# QCopterMV_MCU_Sch.net
KiCad netlist of a schematic drawn in Altium Designer
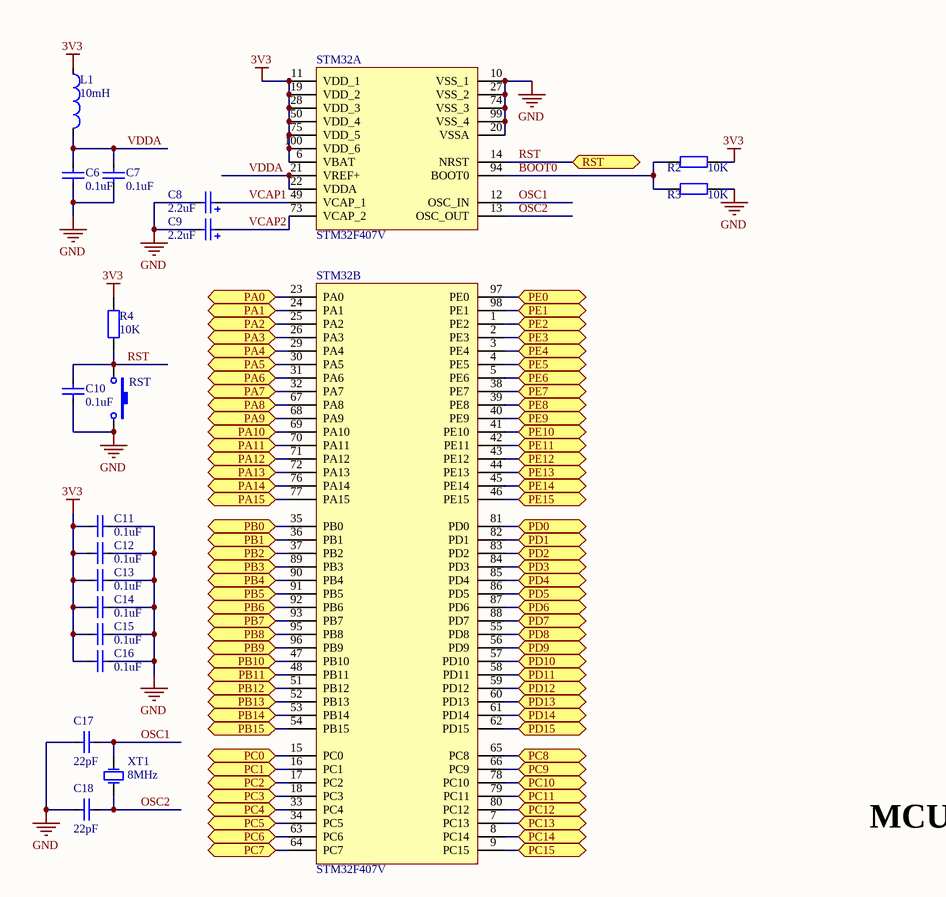
[diagram p0: QCopterMV_MCU_Sch.SchDoc]

(export (version "E")
  (design (tool "Eeschema 10.0.6"))
  (components
    (comp (ref "C6")
      (value "0.1uF")
      (footprint "PCB_Passive:CAP_0603")
      (description "Capacitor")
      (fields (field (name "Comment") "Cap_0603"))
      (libsource (lib "SCH_Passive") (part "Cap_0603"))
    )
    (comp (ref "C7")
      (value "0.1uF")
      (footprint "PCB_Passive:CAP_0603")
      (description "Capacitor")
      (fields (field (name "Comment") "Cap_0603"))
      (libsource (lib "SCH_Passive") (part "Cap_0603"))
    )
    (comp (ref "C8")
      (value "2.2uF")
      (footprint "PCB_Passive:CAP_TAN_P0805")
      (description "Capacitor")
      (fields (field (name "Comment") "Cap_Tan_0805"))
      (libsource (lib "SCH_Passive") (part "Cap_Tan_0805"))
    )
    (comp (ref "C9")
      (value "2.2uF")
      (footprint "PCB_Passive:CAP_TAN_P0805")
      (description "Capacitor")
      (fields (field (name "Comment") "Cap_Tan_0805"))
      (libsource (lib "SCH_Passive") (part "Cap_Tan_0805"))
    )
    (comp (ref "C10")
      (value "0.1uF")
      (footprint "PCB_Passive:CAP_0603")
      (description "Capacitor")
      (fields (field (name "Comment") "Cap_0603"))
      (libsource (lib "SCH_Passive") (part "Cap_0603"))
    )
    (comp (ref "C11")
      (value "0.1uF")
      (footprint "PCB_Passive:CAP_0603")
      (description "Capacitor")
      (fields (field (name "Comment") "Cap_0603"))
      (libsource (lib "SCH_Passive") (part "Cap_0603"))
    )
    (comp (ref "C12")
      (value "0.1uF")
      (footprint "PCB_Passive:CAP_0603")
      (description "Capacitor")
      (fields (field (name "Comment") "Cap_0603"))
      (libsource (lib "SCH_Passive") (part "Cap_0603"))
    )
    (comp (ref "C13")
      (value "0.1uF")
      (footprint "PCB_Passive:CAP_0603")
      (description "Capacitor")
      (fields (field (name "Comment") "Cap_0603"))
      (libsource (lib "SCH_Passive") (part "Cap_0603"))
    )
    (comp (ref "C14")
      (value "0.1uF")
      (footprint "PCB_Passive:CAP_0603")
      (description "Capacitor")
      (fields (field (name "Comment") "Cap_0603"))
      (libsource (lib "SCH_Passive") (part "Cap_0603"))
    )
    (comp (ref "C15")
      (value "0.1uF")
      (footprint "PCB_Passive:CAP_0603")
      (description "Capacitor")
      (fields (field (name "Comment") "Cap_0603"))
      (libsource (lib "SCH_Passive") (part "Cap_0603"))
    )
    (comp (ref "C16")
      (value "0.1uF")
      (footprint "PCB_Passive:CAP_0603")
      (description "Capacitor")
      (fields (field (name "Comment") "Cap_0603"))
      (libsource (lib "SCH_Passive") (part "Cap_0603"))
    )
    (comp (ref "C17")
      (value "22pF")
      (footprint "PCB_Passive:CAP_0603")
      (description "Capacitor")
      (fields (field (name "Comment") "Cap_0603"))
      (libsource (lib "SCH_Passive") (part "Cap_0603"))
    )
    (comp (ref "C18")
      (value "22pF")
      (footprint "PCB_Passive:CAP_0603")
      (description "Capacitor")
      (fields (field (name "Comment") "Cap_0603"))
      (libsource (lib "SCH_Passive") (part "Cap_0603"))
    )
    (comp (ref "L1")
      (value "10mH")
      (footprint "PCB_Passive:IND_0603")
      (description "Inductor")
      (fields (field (name "Comment") "Ind_0603"))
      (libsource (lib "SCH_Passive") (part "Ind_0603"))
    )
    (comp (ref "R2")
      (value "10K")
      (footprint "PCB_Passive:RES_0603")
      (description "Resistor")
      (fields (field (name "Comment") "Res_0603"))
      (libsource (lib "SCH_Passive") (part "Res_0603"))
    )
    (comp (ref "R3")
      (value "10K")
      (footprint "PCB_Passive:RES_0603")
      (description "Resistor")
      (fields (field (name "Comment") "Res_0603"))
      (libsource (lib "SCH_Passive") (part "Res_0603"))
    )
    (comp (ref "R4")
      (value "10K")
      (footprint "PCB_Passive:RES_0603")
      (description "Resistor")
      (fields (field (name "Comment") "Res_0603"))
      (libsource (lib "") (part "Res_0603_1"))
    )
    (comp (ref "RST")
      (value "SW-PB_1")
      (footprint "PCB_Switch:BT_90_T")
      (description "Switch")
      (fields (field (name "PUBLISHER") "Altium Limited"))
      (libsource (lib "SCH_Switch") (part "SW-PB_1"))
    )
    (comp (ref "STM32")
      (value "STM32F407V")
      (footprint "PCB_IC:STM32F_100")
      (description "MCU")
      (libsource (lib "SCH_IC") (part "STM32F407V"))
    )
    (comp (ref "XT1")
      (value "8MHz")
      (footprint "PCB_Oscillator:XTAL_5032")
      (description "Crystal Oscillator")
      (fields (field (name "Comment") "XTAL_5032") (field (name "PUBLISHER") "Altium Limited"))
      (libsource (lib "SCH_Oscillator") (part "XTAL_5032"))
    )
  )
  (nets
    (net (code "1") (name "/BOOT0") (class "Default")
      (node (ref "R2") (pin "1") (pinfunction "1_1") (pintype "passive"))
      (node (ref "R3") (pin "1") (pinfunction "1_1") (pintype "passive"))
      (node (ref "STM32") (pin "94") (pinfunction "BOOT0_94") (pintype "passive"))
    )
    (net (code "2") (name "/OSC1") (class "Default")
      (node (ref "C17") (pin "2") (pinfunction "2_2") (pintype "passive"))
      (node (ref "STM32") (pin "12") (pinfunction "OSC_IN_12") (pintype "passive"))
      (node (ref "XT1") (pin "2") (pinfunction "OSC2_2") (pintype "passive"))
    )
    (net (code "3") (name "/OSC2") (class "Default")
      (node (ref "C18") (pin "2") (pinfunction "2_2") (pintype "passive"))
      (node (ref "STM32") (pin "13") (pinfunction "OSC_OUT_13") (pintype "passive"))
      (node (ref "XT1") (pin "1") (pinfunction "OSC1_1") (pintype "passive"))
    )
    (net (code "4") (name "/PA0") (class "Default")
      (node (ref "STM32") (pin "23") (pinfunction "PA0_23") (pintype "passive"))
    )
    (net (code "5") (name "/PA1") (class "Default")
      (node (ref "STM32") (pin "24") (pinfunction "PA1_24") (pintype "passive"))
    )
    (net (code "6") (name "/PA2") (class "Default")
      (node (ref "STM32") (pin "25") (pinfunction "PA2_25") (pintype "passive"))
    )
    (net (code "7") (name "/PA3") (class "Default")
      (node (ref "STM32") (pin "26") (pinfunction "PA3_26") (pintype "passive"))
    )
    (net (code "8") (name "/PA4") (class "Default")
      (node (ref "STM32") (pin "29") (pinfunction "PA4_29") (pintype "passive"))
    )
    (net (code "9") (name "/PA5") (class "Default")
      (node (ref "STM32") (pin "30") (pinfunction "PA5_30") (pintype "passive"))
    )
    (net (code "10") (name "/PA6") (class "Default")
      (node (ref "STM32") (pin "31") (pinfunction "PA6_31") (pintype "passive"))
    )
    (net (code "11") (name "/PA7") (class "Default")
      (node (ref "STM32") (pin "32") (pinfunction "PA7_32") (pintype "passive"))
    )
    (net (code "12") (name "/PA8") (class "Default")
      (node (ref "STM32") (pin "67") (pinfunction "PA8_67") (pintype "passive"))
    )
    (net (code "13") (name "/PA9") (class "Default")
      (node (ref "STM32") (pin "68") (pinfunction "PA9_68") (pintype "passive"))
    )
    (net (code "14") (name "/PA10") (class "Default")
      (node (ref "STM32") (pin "69") (pinfunction "PA10_69") (pintype "passive"))
    )
    (net (code "15") (name "/PA11") (class "Default")
      (node (ref "STM32") (pin "70") (pinfunction "PA11_70") (pintype "passive"))
    )
    (net (code "16") (name "/PA12") (class "Default")
      (node (ref "STM32") (pin "71") (pinfunction "PA12_71") (pintype "passive"))
    )
    (net (code "17") (name "/PA13") (class "Default")
      (node (ref "STM32") (pin "72") (pinfunction "PA13_72") (pintype "passive"))
    )
    (net (code "18") (name "/PA14") (class "Default")
      (node (ref "STM32") (pin "76") (pinfunction "PA14_76") (pintype "passive"))
    )
    (net (code "19") (name "/PA15") (class "Default")
      (node (ref "STM32") (pin "77") (pinfunction "PA15_77") (pintype "passive"))
    )
    (net (code "20") (name "/PB0") (class "Default")
      (node (ref "STM32") (pin "35") (pinfunction "PB0_35") (pintype "passive"))
    )
    (net (code "21") (name "/PB1") (class "Default")
      (node (ref "STM32") (pin "36") (pinfunction "PB1_36") (pintype "passive"))
    )
    (net (code "22") (name "/PB2") (class "Default")
      (node (ref "STM32") (pin "37") (pinfunction "PB2_37") (pintype "passive"))
    )
    (net (code "23") (name "/PB3") (class "Default")
      (node (ref "STM32") (pin "89") (pinfunction "PB3_89") (pintype "passive"))
    )
    (net (code "24") (name "/PB4") (class "Default")
      (node (ref "STM32") (pin "90") (pinfunction "PB4_90") (pintype "passive"))
    )
    (net (code "25") (name "/PB5") (class "Default")
      (node (ref "STM32") (pin "91") (pinfunction "PB5_91") (pintype "passive"))
    )
    (net (code "26") (name "/PB6") (class "Default")
      (node (ref "STM32") (pin "92") (pinfunction "PB6_92") (pintype "passive"))
    )
    (net (code "27") (name "/PB7") (class "Default")
      (node (ref "STM32") (pin "93") (pinfunction "PB7_93") (pintype "passive"))
    )
    (net (code "28") (name "/PB8") (class "Default")
      (node (ref "STM32") (pin "95") (pinfunction "PB8_95") (pintype "passive"))
    )
    (net (code "29") (name "/PB9") (class "Default")
      (node (ref "STM32") (pin "96") (pinfunction "PB9_96") (pintype "passive"))
    )
    (net (code "30") (name "/PB10") (class "Default")
      (node (ref "STM32") (pin "47") (pinfunction "PB10_47") (pintype "passive"))
    )
    (net (code "31") (name "/PB11") (class "Default")
      (node (ref "STM32") (pin "48") (pinfunction "PB11_48") (pintype "passive"))
    )
    (net (code "32") (name "/PB12") (class "Default")
      (node (ref "STM32") (pin "51") (pinfunction "PB12_51") (pintype "passive"))
    )
    (net (code "33") (name "/PB13") (class "Default")
      (node (ref "STM32") (pin "52") (pinfunction "PB13_52") (pintype "passive"))
    )
    (net (code "34") (name "/PB14") (class "Default")
      (node (ref "STM32") (pin "53") (pinfunction "PB14_53") (pintype "passive"))
    )
    (net (code "35") (name "/PB15") (class "Default")
      (node (ref "STM32") (pin "54") (pinfunction "PB15_54") (pintype "passive"))
    )
    (net (code "36") (name "/PC0") (class "Default")
      (node (ref "STM32") (pin "15") (pinfunction "PC0_15") (pintype "passive"))
    )
    (net (code "37") (name "/PC1") (class "Default")
      (node (ref "STM32") (pin "16") (pinfunction "PC1_16") (pintype "passive"))
    )
    (net (code "38") (name "/PC2") (class "Default")
      (node (ref "STM32") (pin "17") (pinfunction "PC2_17") (pintype "passive"))
    )
    (net (code "39") (name "/PC3") (class "Default")
      (node (ref "STM32") (pin "18") (pinfunction "PC3_18") (pintype "passive"))
    )
    (net (code "40") (name "/PC4") (class "Default")
      (node (ref "STM32") (pin "33") (pinfunction "PC4_33") (pintype "passive"))
    )
    (net (code "41") (name "/PC5") (class "Default")
      (node (ref "STM32") (pin "34") (pinfunction "PC5_34") (pintype "passive"))
    )
    (net (code "42") (name "/PC6") (class "Default")
      (node (ref "STM32") (pin "63") (pinfunction "PC6_63") (pintype "passive"))
    )
    (net (code "43") (name "/PC7") (class "Default")
      (node (ref "STM32") (pin "64") (pinfunction "PC7_64") (pintype "passive"))
    )
    (net (code "44") (name "/PC8") (class "Default")
      (node (ref "STM32") (pin "65") (pinfunction "PC8_65") (pintype "passive"))
    )
    (net (code "45") (name "/PC9") (class "Default")
      (node (ref "STM32") (pin "66") (pinfunction "PC9_66") (pintype "passive"))
    )
    (net (code "46") (name "/PC10") (class "Default")
      (node (ref "STM32") (pin "78") (pinfunction "PC10_78") (pintype "passive"))
    )
    (net (code "47") (name "/PC11") (class "Default")
      (node (ref "STM32") (pin "79") (pinfunction "PC11_79") (pintype "passive"))
    )
    (net (code "48") (name "/PC12") (class "Default")
      (node (ref "STM32") (pin "80") (pinfunction "PC12_80") (pintype "passive"))
    )
    (net (code "49") (name "/PC13") (class "Default")
      (node (ref "STM32") (pin "7") (pinfunction "PC13_7") (pintype "passive"))
    )
    (net (code "50") (name "/PC14") (class "Default")
      (node (ref "STM32") (pin "8") (pinfunction "PC14_8") (pintype "passive"))
    )
    (net (code "51") (name "/PC15") (class "Default")
      (node (ref "STM32") (pin "9") (pinfunction "PC15_9") (pintype "passive"))
    )
    (net (code "52") (name "/PD0") (class "Default")
      (node (ref "STM32") (pin "81") (pinfunction "PD0_81") (pintype "passive"))
    )
    (net (code "53") (name "/PD1") (class "Default")
      (node (ref "STM32") (pin "82") (pinfunction "PD1_82") (pintype "passive"))
    )
    (net (code "54") (name "/PD2") (class "Default")
      (node (ref "STM32") (pin "83") (pinfunction "PD2_83") (pintype "passive"))
    )
    (net (code "55") (name "/PD3") (class "Default")
      (node (ref "STM32") (pin "84") (pinfunction "PD3_84") (pintype "passive"))
    )
    (net (code "56") (name "/PD4") (class "Default")
      (node (ref "STM32") (pin "85") (pinfunction "PD4_85") (pintype "passive"))
    )
    (net (code "57") (name "/PD5") (class "Default")
      (node (ref "STM32") (pin "86") (pinfunction "PD5_86") (pintype "passive"))
    )
    (net (code "58") (name "/PD6") (class "Default")
      (node (ref "STM32") (pin "87") (pinfunction "PD6_87") (pintype "passive"))
    )
    (net (code "59") (name "/PD7") (class "Default")
      (node (ref "STM32") (pin "88") (pinfunction "PD7_88") (pintype "passive"))
    )
    (net (code "60") (name "/PD8") (class "Default")
      (node (ref "STM32") (pin "55") (pinfunction "PD8_55") (pintype "passive"))
    )
    (net (code "61") (name "/PD9") (class "Default")
      (node (ref "STM32") (pin "56") (pinfunction "PD9_56") (pintype "passive"))
    )
    (net (code "62") (name "/PD10") (class "Default")
      (node (ref "STM32") (pin "57") (pinfunction "PD10_57") (pintype "passive"))
    )
    (net (code "63") (name "/PD11") (class "Default")
      (node (ref "STM32") (pin "58") (pinfunction "PD11_58") (pintype "passive"))
    )
    (net (code "64") (name "/PD12") (class "Default")
      (node (ref "STM32") (pin "59") (pinfunction "PD12_59") (pintype "passive"))
    )
    (net (code "65") (name "/PD13") (class "Default")
      (node (ref "STM32") (pin "60") (pinfunction "PD13_60") (pintype "passive"))
    )
    (net (code "66") (name "/PD14") (class "Default")
      (node (ref "STM32") (pin "61") (pinfunction "PD14_61") (pintype "passive"))
    )
    (net (code "67") (name "/PD15") (class "Default")
      (node (ref "STM32") (pin "62") (pinfunction "PD15_62") (pintype "passive"))
    )
    (net (code "68") (name "/PE0") (class "Default")
      (node (ref "STM32") (pin "97") (pinfunction "PE0_97") (pintype "passive"))
    )
    (net (code "69") (name "/PE1") (class "Default")
      (node (ref "STM32") (pin "98") (pinfunction "PE1_98") (pintype "passive"))
    )
    (net (code "70") (name "/PE2") (class "Default")
      (node (ref "STM32") (pin "1") (pinfunction "PE2_1") (pintype "passive"))
    )
    (net (code "71") (name "/PE3") (class "Default")
      (node (ref "STM32") (pin "2") (pinfunction "PE3_2") (pintype "passive"))
    )
    (net (code "72") (name "/PE4") (class "Default")
      (node (ref "STM32") (pin "3") (pinfunction "PE4_3") (pintype "passive"))
    )
    (net (code "73") (name "/PE5") (class "Default")
      (node (ref "STM32") (pin "4") (pinfunction "PE5_4") (pintype "passive"))
    )
    (net (code "74") (name "/PE6") (class "Default")
      (node (ref "STM32") (pin "5") (pinfunction "PE6_5") (pintype "passive"))
    )
    (net (code "75") (name "/PE7") (class "Default")
      (node (ref "STM32") (pin "38") (pinfunction "PE7_38") (pintype "passive"))
    )
    (net (code "76") (name "/PE8") (class "Default")
      (node (ref "STM32") (pin "39") (pinfunction "PE8_39") (pintype "passive"))
    )
    (net (code "77") (name "/PE9") (class "Default")
      (node (ref "STM32") (pin "40") (pinfunction "PE9_40") (pintype "passive"))
    )
    (net (code "78") (name "/PE10") (class "Default")
      (node (ref "STM32") (pin "41") (pinfunction "PE10_41") (pintype "passive"))
    )
    (net (code "79") (name "/PE11") (class "Default")
      (node (ref "STM32") (pin "42") (pinfunction "PE11_42") (pintype "passive"))
    )
    (net (code "80") (name "/PE12") (class "Default")
      (node (ref "STM32") (pin "43") (pinfunction "PE12_43") (pintype "passive"))
    )
    (net (code "81") (name "/PE13") (class "Default")
      (node (ref "STM32") (pin "44") (pinfunction "PE13_44") (pintype "passive"))
    )
    (net (code "82") (name "/PE14") (class "Default")
      (node (ref "STM32") (pin "45") (pinfunction "PE14_45") (pintype "passive"))
    )
    (net (code "83") (name "/PE15") (class "Default")
      (node (ref "STM32") (pin "46") (pinfunction "PE15_46") (pintype "passive"))
    )
    (net (code "84") (name "/RST") (class "Default")
      (node (ref "C10") (pin "1") (pinfunction "1_1") (pintype "passive"))
      (node (ref "R4") (pin "2") (pinfunction "2_2") (pintype "passive"))
      (node (ref "RST") (pin "1") (pinfunction "1_1") (pintype "passive"))
      (node (ref "STM32") (pin "14") (pinfunction "NRST_14") (pintype "passive"))
    )
    (net (code "85") (name "/VCAP1") (class "Default")
      (node (ref "C8") (pin "1") (pinfunction "1_1") (pintype "passive"))
      (node (ref "STM32") (pin "49") (pinfunction "VCAP_1_49") (pintype "passive"))
    )
    (net (code "86") (name "/VCAP2") (class "Default")
      (node (ref "C9") (pin "1") (pinfunction "1_1") (pintype "passive"))
      (node (ref "STM32") (pin "73") (pinfunction "VCAP_2_73") (pintype "passive"))
    )
    (net (code "87") (name "/VDDA") (class "Default")
      (node (ref "C6") (pin "1") (pinfunction "1_1") (pintype "passive"))
      (node (ref "C7") (pin "1") (pinfunction "1_1") (pintype "passive"))
      (node (ref "L1") (pin "2") (pinfunction "2_2") (pintype "passive"))
      (node (ref "STM32") (pin "21") (pinfunction "VREF+_21") (pintype "passive"))
      (node (ref "STM32") (pin "22") (pinfunction "VDDA_22") (pintype "passive"))
    )
    (net (code "88") (name "3V3") (class "Default")
      (node (ref "C11") (pin "2") (pinfunction "2_2") (pintype "passive"))
      (node (ref "C12") (pin "2") (pinfunction "2_2") (pintype "passive"))
      (node (ref "C13") (pin "2") (pinfunction "2_2") (pintype "passive"))
      (node (ref "C14") (pin "2") (pinfunction "2_2") (pintype "passive"))
      (node (ref "C15") (pin "2") (pinfunction "2_2") (pintype "passive"))
      (node (ref "C16") (pin "2") (pinfunction "2_2") (pintype "passive"))
      (node (ref "L1") (pin "1") (pinfunction "1_1") (pintype "passive"))
      (node (ref "R2") (pin "2") (pinfunction "2_2") (pintype "passive"))
      (node (ref "R4") (pin "1") (pinfunction "1_1") (pintype "passive"))
      (node (ref "STM32") (pin "100") (pinfunction "VDD_6_100") (pintype "passive"))
      (node (ref "STM32") (pin "11") (pinfunction "VDD_1_11") (pintype "passive"))
      (node (ref "STM32") (pin "19") (pinfunction "VDD_2_19") (pintype "passive"))
      (node (ref "STM32") (pin "28") (pinfunction "VDD_3_28") (pintype "passive"))
      (node (ref "STM32") (pin "50") (pinfunction "VDD_4_50") (pintype "passive"))
      (node (ref "STM32") (pin "6") (pinfunction "VBAT_6") (pintype "passive"))
      (node (ref "STM32") (pin "75") (pinfunction "VDD_5_75") (pintype "passive"))
    )
    (net (code "89") (name "GND") (class "Default")
      (node (ref "C10") (pin "2") (pinfunction "2_2") (pintype "passive"))
      (node (ref "C11") (pin "1") (pinfunction "1_1") (pintype "passive"))
      (node (ref "C12") (pin "1") (pinfunction "1_1") (pintype "passive"))
      (node (ref "C13") (pin "1") (pinfunction "1_1") (pintype "passive"))
      (node (ref "C14") (pin "1") (pinfunction "1_1") (pintype "passive"))
      (node (ref "C15") (pin "1") (pinfunction "1_1") (pintype "passive"))
      (node (ref "C16") (pin "1") (pinfunction "1_1") (pintype "passive"))
      (node (ref "C17") (pin "1") (pinfunction "1_1") (pintype "passive"))
      (node (ref "C18") (pin "1") (pinfunction "1_1") (pintype "passive"))
      (node (ref "C6") (pin "2") (pinfunction "2_2") (pintype "passive"))
      (node (ref "C7") (pin "2") (pinfunction "2_2") (pintype "passive"))
      (node (ref "C8") (pin "2") (pinfunction "2_2") (pintype "passive"))
      (node (ref "C9") (pin "2") (pinfunction "2_2") (pintype "passive"))
      (node (ref "R3") (pin "2") (pinfunction "2_2") (pintype "passive"))
      (node (ref "RST") (pin "2") (pinfunction "2_2") (pintype "passive"))
      (node (ref "STM32") (pin "10") (pinfunction "VSS_1_10") (pintype "passive"))
      (node (ref "STM32") (pin "20") (pinfunction "VSSA_20") (pintype "passive"))
      (node (ref "STM32") (pin "27") (pinfunction "VSS_2_27") (pintype "passive"))
      (node (ref "STM32") (pin "74") (pinfunction "VSS_3_74") (pintype "passive"))
      (node (ref "STM32") (pin "99") (pinfunction "VSS_4_99") (pintype "passive"))
    )
  )
)
